# nrf_to_serial.net
KiCad netlist of a schematic drawn in EAGLE
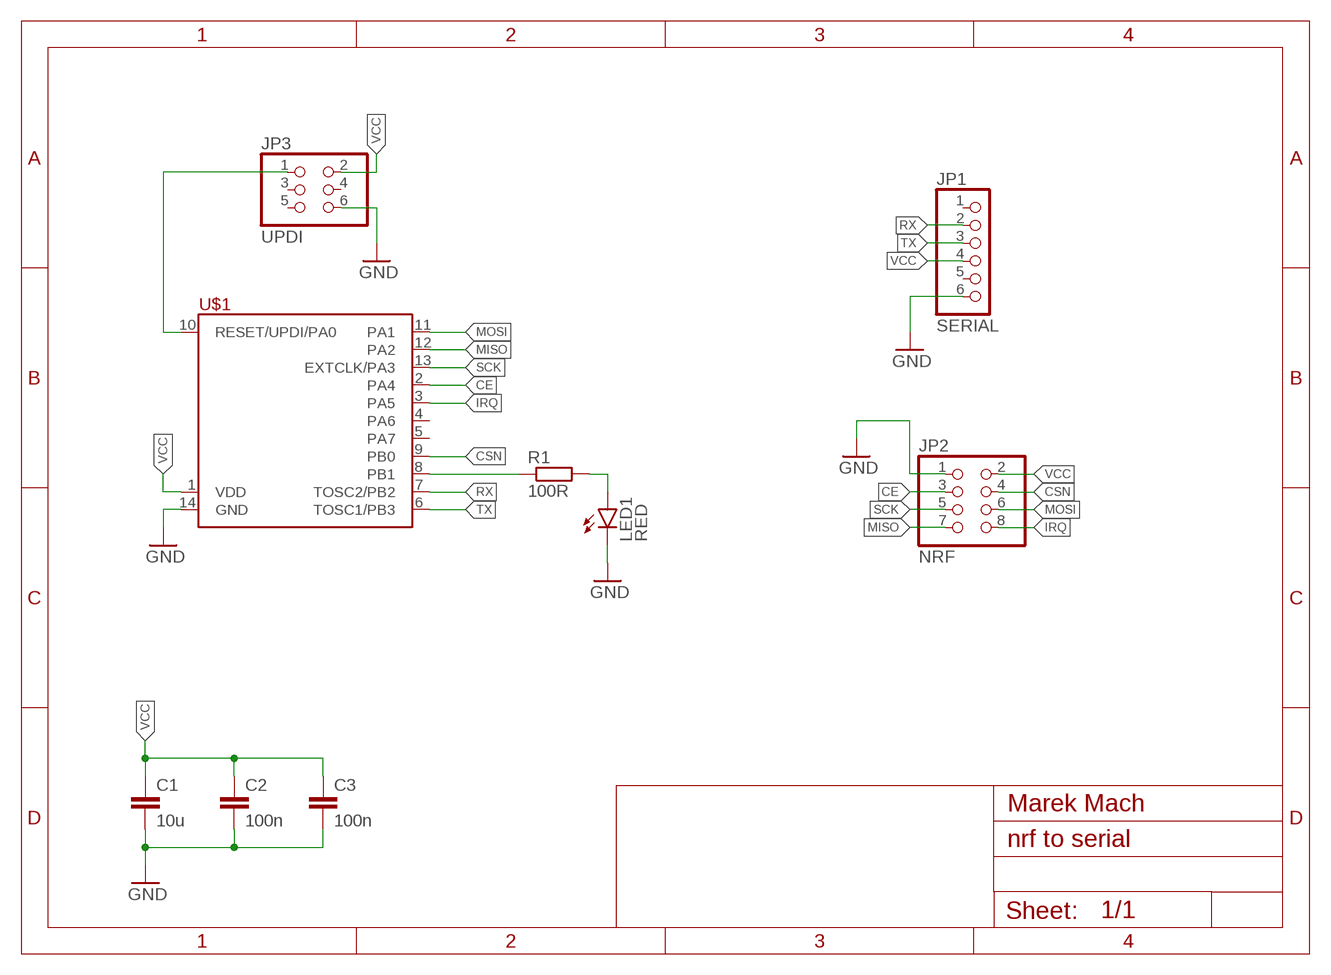
[diagram p0: schematic, sheet 1]

(export (version "E")
  (design (tool "Eeschema 10.0.6"))
  (components
    (comp (ref "C1")
      (value "10u")
      (footprint "eagle-import:C0603")
      (libsource (lib "eagle-import") (part "C-EUC0603"))
    )
    (comp (ref "C2")
      (value "100n")
      (footprint "eagle-import:C0603")
      (libsource (lib "eagle-import") (part "C-EUC0603"))
    )
    (comp (ref "C3")
      (value "100n")
      (footprint "eagle-import:C0603")
      (libsource (lib "eagle-import") (part "C-EUC0603"))
    )
    (comp (ref "JP1")
      (value "SERIAL")
      (footprint "eagle-import:1X06")
      (libsource (lib "eagle-import") (part "PINHD-1X6"))
    )
    (comp (ref "JP2")
      (value "NRF")
      (footprint "eagle-import:2X04")
      (libsource (lib "eagle-import") (part "PINHD-2X4"))
    )
    (comp (ref "JP3")
      (value "UPDI")
      (footprint "eagle-import:2X03")
      (libsource (lib "eagle-import") (part "PINHD-2X3"))
    )
    (comp (ref "LED1")
      (value "RED")
      (footprint "eagle-import:LED3MM")
      (libsource (lib "eagle-import") (part "LED3MM"))
    )
    (comp (ref "R1")
      (value "100R")
      (footprint "eagle-import:R0603")
      (libsource (lib "eagle-import") (part "R-EU_R0603"))
    )
    (comp (ref "U$1")
      (value "TINY214/414/814SOIC")
      (footprint "eagle-import:SOIC14")
      (libsource (lib "eagle-import") (part "TINY214/414/814SOIC"))
    )
  )
  (nets
    (net (code "1") (name "CE") (class "Default")
      (node (ref "JP2") (pin "3") (pinfunction "3_3") (pintype "passive"))
      (node (ref "U$1") (pin "2") (pinfunction "PA4_2") (pintype "bidirectional"))
    )
    (net (code "2") (name "CSN") (class "Default")
      (node (ref "JP2") (pin "4") (pinfunction "4_4") (pintype "passive"))
      (node (ref "U$1") (pin "9") (pinfunction "PB0_9") (pintype "bidirectional"))
    )
    (net (code "3") (name "GND") (class "Default")
      (node (ref "C1") (pin "2") (pinfunction "2_2") (pintype "passive"))
      (node (ref "C2") (pin "2") (pinfunction "2_2") (pintype "passive"))
      (node (ref "C3") (pin "2") (pinfunction "2_2") (pintype "passive"))
      (node (ref "JP1") (pin "6") (pinfunction "6_6") (pintype "passive"))
      (node (ref "JP2") (pin "1") (pinfunction "1_1") (pintype "passive"))
      (node (ref "JP3") (pin "6") (pinfunction "6_6") (pintype "passive"))
      (node (ref "LED1") (pin "K") (pinfunction "C_K") (pintype "passive"))
      (node (ref "U$1") (pin "14") (pinfunction "GND_14") (pintype "power_in"))
    )
    (net (code "4") (name "IRQ") (class "Default")
      (node (ref "JP2") (pin "8") (pinfunction "8_8") (pintype "passive"))
      (node (ref "U$1") (pin "3") (pinfunction "PA5_3") (pintype "bidirectional"))
    )
    (net (code "5") (name "MISO") (class "Default")
      (node (ref "JP2") (pin "7") (pinfunction "7_7") (pintype "passive"))
      (node (ref "U$1") (pin "12") (pinfunction "PA2_12") (pintype "bidirectional"))
    )
    (net (code "6") (name "MOSI") (class "Default")
      (node (ref "JP2") (pin "6") (pinfunction "6_6") (pintype "passive"))
      (node (ref "U$1") (pin "11") (pinfunction "PA1_11") (pintype "bidirectional"))
    )
    (net (code "7") (name "Net-(LED1-PadA)") (class "Default")
      (node (ref "LED1") (pin "A") (pinfunction "A_A") (pintype "passive"))
      (node (ref "R1") (pin "2") (pinfunction "2_2") (pintype "passive"))
    )
    (net (code "8") (name "Net-(U$1-PB1)") (class "Default")
      (node (ref "R1") (pin "1") (pinfunction "1_1") (pintype "passive"))
      (node (ref "U$1") (pin "8") (pinfunction "PB1_8") (pintype "bidirectional"))
    )
    (net (code "9") (name "Net-(U$1-RESET{slash}UPDI{slash}PA0)") (class "Default")
      (node (ref "JP3") (pin "1") (pinfunction "1_1") (pintype "passive"))
      (node (ref "U$1") (pin "10") (pinfunction "RESET/UPDI/PA0_10") (pintype "bidirectional"))
    )
    (net (code "10") (name "RX") (class "Default")
      (node (ref "JP1") (pin "2") (pinfunction "2_2") (pintype "passive"))
      (node (ref "U$1") (pin "7") (pinfunction "TOSC2/PB2_7") (pintype "bidirectional"))
    )
    (net (code "11") (name "SCK") (class "Default")
      (node (ref "JP2") (pin "5") (pinfunction "5_5") (pintype "passive"))
      (node (ref "U$1") (pin "13") (pinfunction "EXTCLK/PA3_13") (pintype "bidirectional"))
    )
    (net (code "12") (name "TX") (class "Default")
      (node (ref "JP1") (pin "3") (pinfunction "3_3") (pintype "passive"))
      (node (ref "U$1") (pin "6") (pinfunction "TOSC1/PB3_6") (pintype "bidirectional"))
    )
    (net (code "13") (name "VCC") (class "Default")
      (node (ref "C1") (pin "1") (pinfunction "1_1") (pintype "passive"))
      (node (ref "C2") (pin "1") (pinfunction "1_1") (pintype "passive"))
      (node (ref "C3") (pin "1") (pinfunction "1_1") (pintype "passive"))
      (node (ref "JP1") (pin "4") (pinfunction "4_4") (pintype "passive"))
      (node (ref "JP2") (pin "2") (pinfunction "2_2") (pintype "passive"))
      (node (ref "JP3") (pin "2") (pinfunction "2_2") (pintype "passive"))
      (node (ref "U$1") (pin "1") (pinfunction "VDD_1") (pintype "power_in"))
    )
    (net (code "14") (name "unconnected-(JP1-Pad1)") (class "Default")
      (node (ref "JP1") (pin "1") (pinfunction "1_1") (pintype "passive"))
    )
    (net (code "15") (name "unconnected-(JP1-Pad5)") (class "Default")
      (node (ref "JP1") (pin "5") (pinfunction "5_5") (pintype "passive"))
    )
    (net (code "16") (name "unconnected-(JP3-Pad3)") (class "Default")
      (node (ref "JP3") (pin "3") (pinfunction "3_3") (pintype "passive"))
    )
    (net (code "17") (name "unconnected-(JP3-Pad4)") (class "Default")
      (node (ref "JP3") (pin "4") (pinfunction "4_4") (pintype "passive"))
    )
    (net (code "18") (name "unconnected-(JP3-Pad5)") (class "Default")
      (node (ref "JP3") (pin "5") (pinfunction "5_5") (pintype "passive"))
    )
    (net (code "19") (name "unconnected-(U$1-PA6-Pad4)") (class "Default")
      (node (ref "U$1") (pin "4") (pinfunction "PA6_4") (pintype "bidirectional"))
    )
    (net (code "20") (name "unconnected-(U$1-PA7-Pad5)") (class "Default")
      (node (ref "U$1") (pin "5") (pinfunction "PA7_5") (pintype "bidirectional"))
    )
  )
)
